# connector_interface.net
KiCad netlist of a schematic drawn in EAGLE
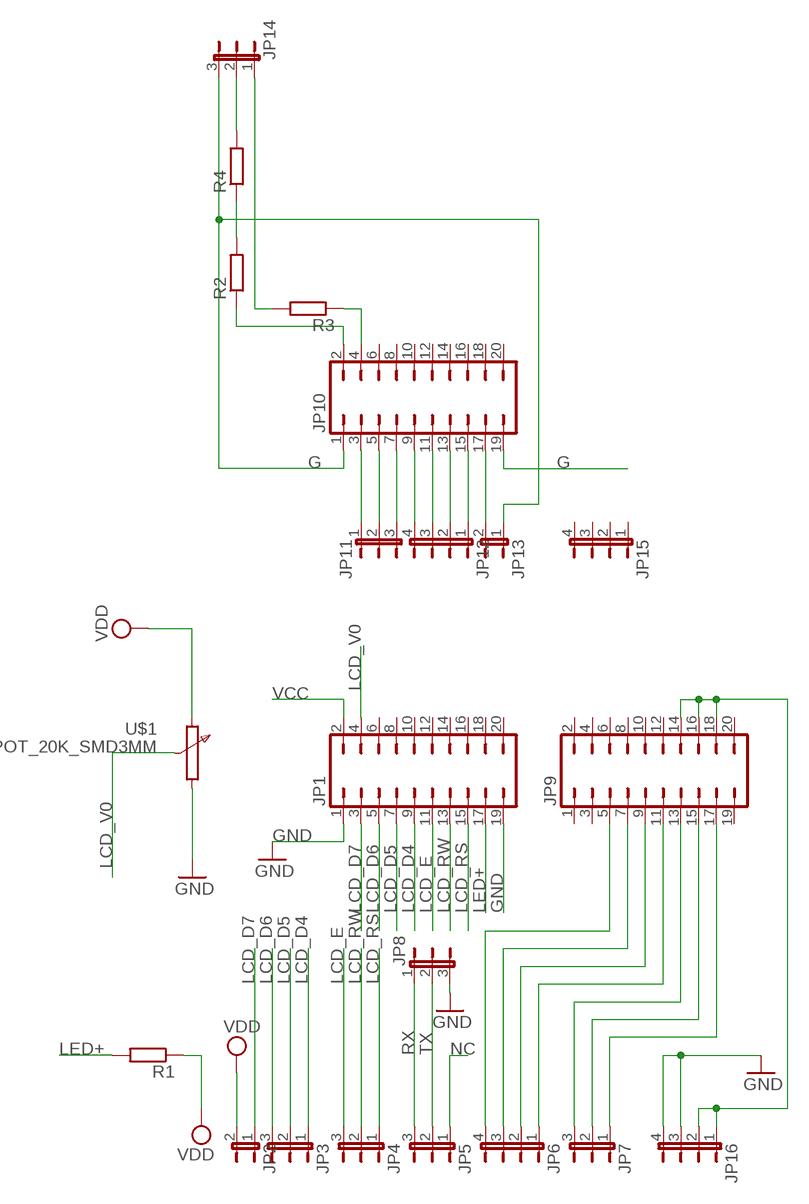
[diagram p0: schematic, sheet 1]

(export (version "E")
  (design (tool "Eeschema 10.0.6"))
  (components
    (comp (ref "JP1")
      (value "JP10Q")
      (footprint "eagle-import:JP10Q")
      (libsource (lib "eagle-import") (part "JP10Q"))
    )
    (comp (ref "JP2")
      (value "JP1E")
      (footprint "eagle-import:JP1")
      (libsource (lib "eagle-import") (part "JP1E"))
    )
    (comp (ref "JP3")
      (value "JP2E")
      (footprint "eagle-import:JP2")
      (libsource (lib "eagle-import") (part "JP2E"))
    )
    (comp (ref "JP4")
      (value "JP2E")
      (footprint "eagle-import:JP2")
      (libsource (lib "eagle-import") (part "JP2E"))
    )
    (comp (ref "JP5")
      (value "JP2E")
      (footprint "eagle-import:JP2")
      (libsource (lib "eagle-import") (part "JP2E"))
    )
    (comp (ref "JP6")
      (value "JP4E")
      (footprint "eagle-import:JP4")
      (libsource (lib "eagle-import") (part "JP4E"))
    )
    (comp (ref "JP7")
      (value "JP2E")
      (footprint "eagle-import:JP2")
      (libsource (lib "eagle-import") (part "JP2E"))
    )
    (comp (ref "JP8")
      (value "JP2E")
      (footprint "eagle-import:JP2")
      (libsource (lib "eagle-import") (part "JP2E"))
    )
    (comp (ref "JP9")
      (value "JP10Q")
      (footprint "eagle-import:JP10Q")
      (libsource (lib "eagle-import") (part "JP10Q"))
    )
    (comp (ref "JP10")
      (value "JP10Q")
      (footprint "eagle-import:JP10Q")
      (libsource (lib "eagle-import") (part "JP10Q"))
    )
    (comp (ref "JP11")
      (value "JP2E")
      (footprint "eagle-import:JP2")
      (libsource (lib "eagle-import") (part "JP2E"))
    )
    (comp (ref "JP12")
      (value "JP4E")
      (footprint "eagle-import:JP4")
      (libsource (lib "eagle-import") (part "JP4E"))
    )
    (comp (ref "JP13")
      (value "JP1E")
      (footprint "eagle-import:JP1")
      (libsource (lib "eagle-import") (part "JP1E"))
    )
    (comp (ref "JP14")
      (value "JP2E")
      (footprint "eagle-import:JP2")
      (libsource (lib "eagle-import") (part "JP2E"))
    )
    (comp (ref "JP15")
      (value "JP4E")
      (footprint "eagle-import:JP4")
      (libsource (lib "eagle-import") (part "JP4E"))
    )
    (comp (ref "JP16")
      (value "JP4E")
      (footprint "eagle-import:JP4")
      (libsource (lib "eagle-import") (part "JP4E"))
    )
    (comp (ref "R1")
      (value "R-EU_R1206")
      (footprint "eagle-import:R1206")
      (libsource (lib "eagle-import") (part "R-EU_R1206"))
    )
    (comp (ref "R2")
      (value "R-EU_R1206")
      (footprint "eagle-import:R1206")
      (libsource (lib "eagle-import") (part "R-EU_R1206"))
    )
    (comp (ref "R3")
      (value "R-EU_R1206")
      (footprint "eagle-import:R1206")
      (libsource (lib "eagle-import") (part "R-EU_R1206"))
    )
    (comp (ref "R4")
      (value "R-EU_R1206")
      (footprint "eagle-import:R1206")
      (libsource (lib "eagle-import") (part "R-EU_R1206"))
    )
    (comp (ref "U$1")
      (value "POT_20K_SMD3MM")
      (footprint "eagle-import:POT_3MM_SMD")
      (libsource (lib "eagle-import") (part "POT_20K_SMD3MM"))
    )
  )
  (nets
    (net (code "1") (name "/G") (class "Default")
      (node (ref "JP10") (pin "1") (pinfunction "1_1") (pintype "passive"))
      (node (ref "JP10") (pin "19") (pinfunction "19_19") (pintype "passive"))
      (node (ref "JP13") (pin "1") (pinfunction "1_1") (pintype "passive"))
      (node (ref "JP14") (pin "3") (pinfunction "3_3") (pintype "passive"))
    )
    (net (code "2") (name "/LCD_D4") (class "Default")
      (node (ref "JP1") (pin "9") (pinfunction "9_9") (pintype "passive"))
      (node (ref "JP3") (pin "1") (pinfunction "1_1") (pintype "passive"))
    )
    (net (code "3") (name "/LCD_D5") (class "Default")
      (node (ref "JP1") (pin "7") (pinfunction "7_7") (pintype "passive"))
      (node (ref "JP3") (pin "2") (pinfunction "2_2") (pintype "passive"))
    )
    (net (code "4") (name "/LCD_D6") (class "Default")
      (node (ref "JP1") (pin "5") (pinfunction "5_5") (pintype "passive"))
      (node (ref "JP3") (pin "3") (pinfunction "3_3") (pintype "passive"))
    )
    (net (code "5") (name "/LCD_D7") (class "Default")
      (node (ref "JP1") (pin "3") (pinfunction "3_3") (pintype "passive"))
      (node (ref "JP2") (pin "1") (pinfunction "1_1") (pintype "passive"))
    )
    (net (code "6") (name "/LCD_E") (class "Default")
      (node (ref "JP1") (pin "11") (pinfunction "11_11") (pintype "passive"))
      (node (ref "JP4") (pin "3") (pinfunction "3_3") (pintype "passive"))
    )
    (net (code "7") (name "/LCD_RS") (class "Default")
      (node (ref "JP1") (pin "15") (pinfunction "15_15") (pintype "passive"))
      (node (ref "JP4") (pin "1") (pinfunction "1_1") (pintype "passive"))
    )
    (net (code "8") (name "/LCD_RW") (class "Default")
      (node (ref "JP1") (pin "13") (pinfunction "13_13") (pintype "passive"))
      (node (ref "JP4") (pin "2") (pinfunction "2_2") (pintype "passive"))
    )
    (net (code "9") (name "/LCD_V0") (class "Default")
      (node (ref "JP1") (pin "4") (pinfunction "4_4") (pintype "passive"))
      (node (ref "U$1") (pin "2") (pinfunction "P$2_2") (pintype "bidirectional"))
    )
    (net (code "10") (name "/LED+") (class "Default")
      (node (ref "JP1") (pin "17") (pinfunction "17_17") (pintype "passive"))
      (node (ref "R1") (pin "2") (pinfunction "2_2") (pintype "passive"))
    )
    (net (code "11") (name "/NC") (class "Default")
      (node (ref "JP5") (pin "1") (pinfunction "1_1") (pintype "passive"))
    )
    (net (code "12") (name "/RX") (class "Default")
      (node (ref "JP5") (pin "3") (pinfunction "3_3") (pintype "passive"))
      (node (ref "JP8") (pin "1") (pinfunction "1_1") (pintype "passive"))
    )
    (net (code "13") (name "/TX") (class "Default")
      (node (ref "JP5") (pin "2") (pinfunction "2_2") (pintype "passive"))
      (node (ref "JP8") (pin "2") (pinfunction "2_2") (pintype "passive"))
    )
    (net (code "14") (name "/VCC") (class "Default")
      (node (ref "JP1") (pin "2") (pinfunction "2_2") (pintype "passive"))
    )
    (net (code "15") (name "GND") (class "Default")
      (node (ref "JP1") (pin "1") (pinfunction "1_1") (pintype "passive"))
      (node (ref "JP1") (pin "19") (pinfunction "19_19") (pintype "passive"))
      (node (ref "JP16") (pin "3") (pinfunction "3_3") (pintype "passive"))
      (node (ref "JP16") (pin "4") (pinfunction "4_4") (pintype "passive"))
      (node (ref "JP8") (pin "3") (pinfunction "3_3") (pintype "passive"))
      (node (ref "U$1") (pin "1") (pinfunction "P$1_1") (pintype "bidirectional"))
    )
    (net (code "16") (name "Net-(JP6-Pad1)") (class "Default")
      (node (ref "JP6") (pin "1") (pinfunction "1_1") (pintype "passive"))
      (node (ref "JP9") (pin "11") (pinfunction "11_11") (pintype "passive"))
    )
    (net (code "17") (name "Net-(JP6-Pad2)") (class "Default")
      (node (ref "JP6") (pin "2") (pinfunction "2_2") (pintype "passive"))
      (node (ref "JP9") (pin "9") (pinfunction "9_9") (pintype "passive"))
    )
    (net (code "18") (name "Net-(JP6-Pad3)") (class "Default")
      (node (ref "JP6") (pin "3") (pinfunction "3_3") (pintype "passive"))
      (node (ref "JP9") (pin "7") (pinfunction "7_7") (pintype "passive"))
    )
    (net (code "19") (name "Net-(JP6-Pad4)") (class "Default")
      (node (ref "JP6") (pin "4") (pinfunction "4_4") (pintype "passive"))
      (node (ref "JP9") (pin "5") (pinfunction "5_5") (pintype "passive"))
    )
    (net (code "20") (name "Net-(JP7-Pad1)") (class "Default")
      (node (ref "JP7") (pin "1") (pinfunction "1_1") (pintype "passive"))
      (node (ref "JP9") (pin "17") (pinfunction "17_17") (pintype "passive"))
    )
    (net (code "21") (name "Net-(JP7-Pad2)") (class "Default")
      (node (ref "JP7") (pin "2") (pinfunction "2_2") (pintype "passive"))
      (node (ref "JP9") (pin "15") (pinfunction "15_15") (pintype "passive"))
    )
    (net (code "22") (name "Net-(JP7-Pad3)") (class "Default")
      (node (ref "JP7") (pin "3") (pinfunction "3_3") (pintype "passive"))
      (node (ref "JP9") (pin "13") (pinfunction "13_13") (pintype "passive"))
    )
    (net (code "23") (name "Net-(JP10-Pad2)") (class "Default")
      (node (ref "JP10") (pin "2") (pinfunction "2_2") (pintype "passive"))
      (node (ref "R2") (pin "1") (pinfunction "1_1") (pintype "passive"))
    )
    (net (code "24") (name "Net-(JP10-Pad3)") (class "Default")
      (node (ref "JP10") (pin "3") (pinfunction "3_3") (pintype "passive"))
      (node (ref "JP11") (pin "1") (pinfunction "1_1") (pintype "passive"))
    )
    (net (code "25") (name "Net-(JP10-Pad4)") (class "Default")
      (node (ref "JP10") (pin "4") (pinfunction "4_4") (pintype "passive"))
      (node (ref "R3") (pin "1") (pinfunction "1_1") (pintype "passive"))
    )
    (net (code "26") (name "Net-(JP10-Pad5)") (class "Default")
      (node (ref "JP10") (pin "5") (pinfunction "5_5") (pintype "passive"))
      (node (ref "JP11") (pin "2") (pinfunction "2_2") (pintype "passive"))
    )
    (net (code "27") (name "Net-(JP10-Pad7)") (class "Default")
      (node (ref "JP10") (pin "7") (pinfunction "7_7") (pintype "passive"))
      (node (ref "JP11") (pin "3") (pinfunction "3_3") (pintype "passive"))
    )
    (net (code "28") (name "Net-(JP10-Pad9)") (class "Default")
      (node (ref "JP10") (pin "9") (pinfunction "9_9") (pintype "passive"))
      (node (ref "JP12") (pin "4") (pinfunction "4_4") (pintype "passive"))
    )
    (net (code "29") (name "Net-(JP10-Pad11)") (class "Default")
      (node (ref "JP10") (pin "11") (pinfunction "11_11") (pintype "passive"))
      (node (ref "JP12") (pin "3") (pinfunction "3_3") (pintype "passive"))
    )
    (net (code "30") (name "Net-(JP10-Pad13)") (class "Default")
      (node (ref "JP10") (pin "13") (pinfunction "13_13") (pintype "passive"))
      (node (ref "JP12") (pin "2") (pinfunction "2_2") (pintype "passive"))
    )
    (net (code "31") (name "Net-(JP10-Pad15)") (class "Default")
      (node (ref "JP10") (pin "15") (pinfunction "15_15") (pintype "passive"))
      (node (ref "JP12") (pin "1") (pinfunction "1_1") (pintype "passive"))
    )
    (net (code "32") (name "Net-(JP10-Pad17)") (class "Default")
      (node (ref "JP10") (pin "17") (pinfunction "17_17") (pintype "passive"))
      (node (ref "JP13") (pin "2") (pinfunction "2_2") (pintype "passive"))
    )
    (net (code "33") (name "Net-(JP14-Pad1)") (class "Default")
      (node (ref "JP14") (pin "1") (pinfunction "1_1") (pintype "passive"))
      (node (ref "R3") (pin "2") (pinfunction "2_2") (pintype "passive"))
    )
    (net (code "34") (name "Net-(JP14-Pad2)") (class "Default")
      (node (ref "JP14") (pin "2") (pinfunction "2_2") (pintype "passive"))
      (node (ref "R4") (pin "2") (pinfunction "2_2") (pintype "passive"))
    )
    (net (code "35") (name "Net-(JP16-Pad1)") (class "Default")
      (node (ref "JP16") (pin "1") (pinfunction "1_1") (pintype "passive"))
      (node (ref "JP16") (pin "2") (pinfunction "2_2") (pintype "passive"))
      (node (ref "JP9") (pin "14") (pinfunction "14_14") (pintype "passive"))
      (node (ref "JP9") (pin "16") (pinfunction "16_16") (pintype "passive"))
      (node (ref "JP9") (pin "18") (pinfunction "18_18") (pintype "passive"))
    )
    (net (code "36") (name "Net-(R2-Pad2)") (class "Default")
      (node (ref "R2") (pin "2") (pinfunction "2_2") (pintype "passive"))
      (node (ref "R4") (pin "1") (pinfunction "1_1") (pintype "passive"))
    )
    (net (code "37") (name "VDD") (class "Default")
      (node (ref "JP2") (pin "2") (pinfunction "2_2") (pintype "passive"))
      (node (ref "R1") (pin "1") (pinfunction "1_1") (pintype "passive"))
      (node (ref "U$1") (pin "3") (pinfunction "P$3_3") (pintype "passive"))
    )
    (net (code "38") (name "unconnected-(JP1-Pad6)") (class "Default")
      (node (ref "JP1") (pin "6") (pinfunction "6_6") (pintype "passive"))
    )
    (net (code "39") (name "unconnected-(JP1-Pad8)") (class "Default")
      (node (ref "JP1") (pin "8") (pinfunction "8_8") (pintype "passive"))
    )
    (net (code "40") (name "unconnected-(JP1-Pad10)") (class "Default")
      (node (ref "JP1") (pin "10") (pinfunction "10_10") (pintype "passive"))
    )
    (net (code "41") (name "unconnected-(JP1-Pad12)") (class "Default")
      (node (ref "JP1") (pin "12") (pinfunction "12_12") (pintype "passive"))
    )
    (net (code "42") (name "unconnected-(JP1-Pad14)") (class "Default")
      (node (ref "JP1") (pin "14") (pinfunction "14_14") (pintype "passive"))
    )
    (net (code "43") (name "unconnected-(JP1-Pad16)") (class "Default")
      (node (ref "JP1") (pin "16") (pinfunction "16_16") (pintype "passive"))
    )
    (net (code "44") (name "unconnected-(JP1-Pad18)") (class "Default")
      (node (ref "JP1") (pin "18") (pinfunction "18_18") (pintype "passive"))
    )
    (net (code "45") (name "unconnected-(JP1-Pad20)") (class "Default")
      (node (ref "JP1") (pin "20") (pinfunction "20_20") (pintype "passive"))
    )
    (net (code "46") (name "unconnected-(JP9-Pad1)") (class "Default")
      (node (ref "JP9") (pin "1") (pinfunction "1_1") (pintype "passive"))
    )
    (net (code "47") (name "unconnected-(JP9-Pad2)") (class "Default")
      (node (ref "JP9") (pin "2") (pinfunction "2_2") (pintype "passive"))
    )
    (net (code "48") (name "unconnected-(JP9-Pad3)") (class "Default")
      (node (ref "JP9") (pin "3") (pinfunction "3_3") (pintype "passive"))
    )
    (net (code "49") (name "unconnected-(JP9-Pad4)") (class "Default")
      (node (ref "JP9") (pin "4") (pinfunction "4_4") (pintype "passive"))
    )
    (net (code "50") (name "unconnected-(JP9-Pad6)") (class "Default")
      (node (ref "JP9") (pin "6") (pinfunction "6_6") (pintype "passive"))
    )
    (net (code "51") (name "unconnected-(JP9-Pad8)") (class "Default")
      (node (ref "JP9") (pin "8") (pinfunction "8_8") (pintype "passive"))
    )
    (net (code "52") (name "unconnected-(JP9-Pad10)") (class "Default")
      (node (ref "JP9") (pin "10") (pinfunction "10_10") (pintype "passive"))
    )
    (net (code "53") (name "unconnected-(JP9-Pad12)") (class "Default")
      (node (ref "JP9") (pin "12") (pinfunction "12_12") (pintype "passive"))
    )
    (net (code "54") (name "unconnected-(JP9-Pad19)") (class "Default")
      (node (ref "JP9") (pin "19") (pinfunction "19_19") (pintype "passive"))
    )
    (net (code "55") (name "unconnected-(JP9-Pad20)") (class "Default")
      (node (ref "JP9") (pin "20") (pinfunction "20_20") (pintype "passive"))
    )
    (net (code "56") (name "unconnected-(JP10-Pad6)") (class "Default")
      (node (ref "JP10") (pin "6") (pinfunction "6_6") (pintype "passive"))
    )
    (net (code "57") (name "unconnected-(JP10-Pad8)") (class "Default")
      (node (ref "JP10") (pin "8") (pinfunction "8_8") (pintype "passive"))
    )
    (net (code "58") (name "unconnected-(JP10-Pad10)") (class "Default")
      (node (ref "JP10") (pin "10") (pinfunction "10_10") (pintype "passive"))
    )
    (net (code "59") (name "unconnected-(JP10-Pad12)") (class "Default")
      (node (ref "JP10") (pin "12") (pinfunction "12_12") (pintype "passive"))
    )
    (net (code "60") (name "unconnected-(JP10-Pad14)") (class "Default")
      (node (ref "JP10") (pin "14") (pinfunction "14_14") (pintype "passive"))
    )
    (net (code "61") (name "unconnected-(JP10-Pad16)") (class "Default")
      (node (ref "JP10") (pin "16") (pinfunction "16_16") (pintype "passive"))
    )
    (net (code "62") (name "unconnected-(JP10-Pad18)") (class "Default")
      (node (ref "JP10") (pin "18") (pinfunction "18_18") (pintype "passive"))
    )
    (net (code "63") (name "unconnected-(JP10-Pad20)") (class "Default")
      (node (ref "JP10") (pin "20") (pinfunction "20_20") (pintype "passive"))
    )
    (net (code "64") (name "unconnected-(JP15-Pad1)") (class "Default")
      (node (ref "JP15") (pin "1") (pinfunction "1_1") (pintype "passive"))
    )
    (net (code "65") (name "unconnected-(JP15-Pad2)") (class "Default")
      (node (ref "JP15") (pin "2") (pinfunction "2_2") (pintype "passive"))
    )
    (net (code "66") (name "unconnected-(JP15-Pad3)") (class "Default")
      (node (ref "JP15") (pin "3") (pinfunction "3_3") (pintype "passive"))
    )
    (net (code "67") (name "unconnected-(JP15-Pad4)") (class "Default")
      (node (ref "JP15") (pin "4") (pinfunction "4_4") (pintype "passive"))
    )
  )
)
